# Gero_Board2.net
KiCad netlist of a schematic drawn in Altium Designer
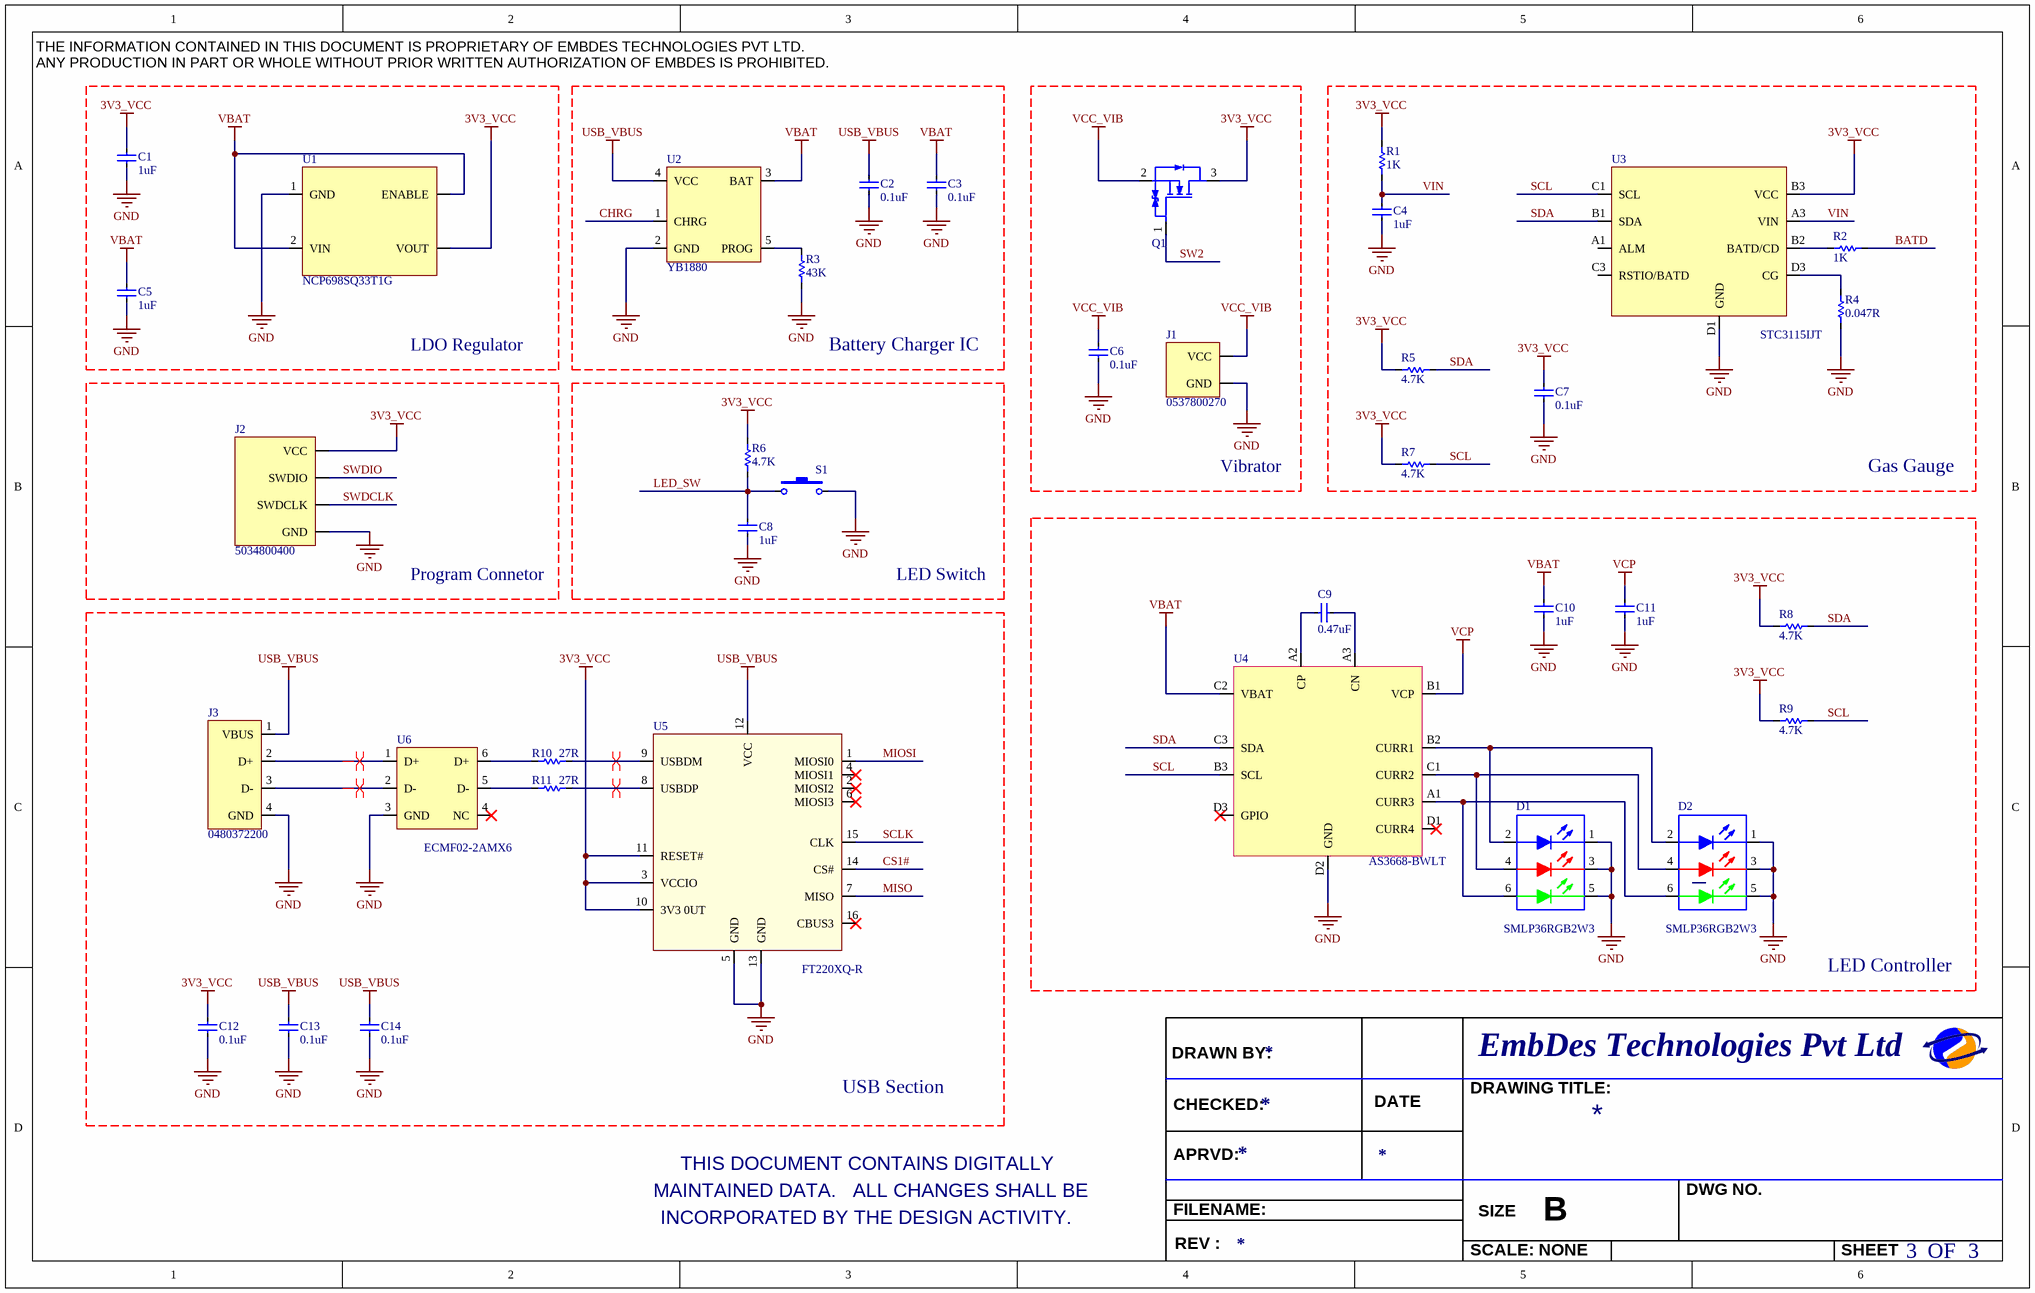
[diagram p0: Gero_Board2.SchDoc]

(export (version "E")
  (design (tool "Eeschema 10.0.6"))
  (components
    (comp (ref "C1")
      (value "1uF")
      (footprint "CAPC1005X04L")
      (description "CAP CER 1UF 16V 10% X5R 0402")
      (fields
        (field (name "MANUFACTURER") "TDK Corporation")
        (field (name "MANUFACTURER PART NUMBER") "C1005X5R1C105K050BC")
      )
      (libsource (lib "Gero_Board.~(283)") (part "CAP CER 1UF 16V 10% X5R 0402"))
    )
    (comp (ref "C2")
      (value "0.1uF")
      (footprint "CAPC1005X04L")
      (description "CAP CER 0.1UF 16V 10% X5R 0201")
      (fields
        (field (name "MANUFACTURER") "TDK Corporation")
        (field (name "MANUFACTURER PART NUMBER") "C0603X5R1C104K030BC")
      )
      (libsource (lib "Gero_Board") (part "CAP CER 0.1UF 16V 10% X5R 0201"))
    )
    (comp (ref "C3")
      (value "0.1uF")
      (footprint "CAPC1005X04L")
      (description "CAP CER 0.1UF 16V 10% X5R 0201")
      (fields
        (field (name "MANUFACTURER") "TDK Corporation")
        (field (name "MANUFACTURER PART NUMBER") "C0603X5R1C104K030BC")
      )
      (libsource (lib "Gero_Board") (part "CAP CER 0.1UF 16V 10% X5R 0201"))
    )
    (comp (ref "C4")
      (value "1uF")
      (footprint "CAPC1005X04L")
      (description "CAP CER 1UF 16V 10% X5R 0402")
      (fields
        (field (name "MANUFACTURER") "TDK Corporation")
        (field (name "MANUFACTURER PART NUMBER") "C1005X5R1C105K050BC")
      )
      (libsource (lib "Gero_Board.~(283)") (part "CAP CER 1UF 16V 10% X5R 0402"))
    )
    (comp (ref "C5")
      (value "1uF")
      (footprint "CAPC1005X04L")
      (description "CAP CER 1UF 16V 10% X5R 0402")
      (fields
        (field (name "MANUFACTURER") "TDK Corporation")
        (field (name "MANUFACTURER PART NUMBER") "C1005X5R1C105K050BC")
      )
      (libsource (lib "Gero_Board.~(283)") (part "CAP CER 1UF 16V 10% X5R 0402"))
    )
    (comp (ref "C6")
      (value "0.1uF")
      (footprint "CAPC1005X04L")
      (description "CAP CER 0.1UF 16V 10% X5R 0201")
      (fields
        (field (name "MANUFACTURER") "TDK Corporation")
        (field (name "MANUFACTURER PART NUMBER") "C0603X5R1C104K030BC")
      )
      (libsource (lib "Gero_Board") (part "CAP CER 0.1UF 16V 10% X5R 0201"))
    )
    (comp (ref "C7")
      (value "0.1uF")
      (footprint "CAPC1005X04L")
      (description "CAP CER 0.1UF 16V 10% X5R 0201")
      (fields
        (field (name "MANUFACTURER") "TDK Corporation")
        (field (name "MANUFACTURER PART NUMBER") "C0603X5R1C104K030BC")
      )
      (libsource (lib "Gero_Board") (part "CAP CER 0.1UF 16V 10% X5R 0201"))
    )
    (comp (ref "C8")
      (value "1uF")
      (footprint "CAPC1005X04L")
      (description "CAP CER 1UF 16V 10% X5R 0402")
      (fields
        (field (name "MANUFACTURER") "TDK Corporation")
        (field (name "MANUFACTURER PART NUMBER") "C1005X5R1C105K050BC")
      )
      (libsource (lib "Gero_Board.~(283)") (part "CAP CER 1UF 16V 10% X5R 0402"))
    )
    (comp (ref "C9")
      (value "0.47uF")
      (footprint "CAPC1005X04L")
      (description "CAP CER 0.47UF 10V 20% JB 0201")
      (fields
        (field (name "MANUFACTURER") "TDK Corporation")
        (field (name "MANUFACTURER PART NUMBER") "C0603JB1A474M030BC")
      )
      (libsource (lib "Gero_Board") (part "CAP CER 0.47UF 10V 20% JB 0201"))
    )
    (comp (ref "C10")
      (value "1uF")
      (footprint "CAPC1005X04L")
      (description "CAP CER 1UF 16V 10% X5R 0402")
      (fields
        (field (name "MANUFACTURER") "TDK Corporation")
        (field (name "MANUFACTURER PART NUMBER") "C1005X5R1C105K050BC")
      )
      (libsource (lib "Gero_Board.~(283)") (part "CAP CER 1UF 16V 10% X5R 0402"))
    )
    (comp (ref "C11")
      (value "1uF")
      (footprint "CAPC1005X04L")
      (description "CAP CER 1UF 16V 10% X5R 0402")
      (fields
        (field (name "MANUFACTURER") "TDK Corporation")
        (field (name "MANUFACTURER PART NUMBER") "C1005X5R1C105K050BC")
      )
      (libsource (lib "Gero_Board.~(283)") (part "CAP CER 1UF 16V 10% X5R 0402"))
    )
    (comp (ref "C12")
      (value "0.1uF")
      (footprint "CAPC1005X04L")
      (description "CAP CER 0.1UF 16V 10% X5R 0201")
      (fields
        (field (name "MANUFACTURER") "TDK Corporation")
        (field (name "MANUFACTURER PART NUMBER") "C0603X5R1C104K030BC")
      )
      (libsource (lib "Gero_Board") (part "CAP CER 0.1UF 16V 10% X5R 0201"))
    )
    (comp (ref "C13")
      (value "0.1uF")
      (footprint "CAPC1005X04L")
      (description "CAP CER 0.1UF 16V 10% X5R 0201")
      (fields
        (field (name "MANUFACTURER") "TDK Corporation")
        (field (name "MANUFACTURER PART NUMBER") "C0603X5R1C104K030BC")
      )
      (libsource (lib "Gero_Board") (part "CAP CER 0.1UF 16V 10% X5R 0201"))
    )
    (comp (ref "C14")
      (value "0.1uF")
      (footprint "CAPC1005X04L")
      (description "CAP CER 0.1UF 16V 10% X5R 0201")
      (fields
        (field (name "MANUFACTURER") "TDK Corporation")
        (field (name "MANUFACTURER PART NUMBER") "C0603X5R1C104K030BC")
      )
      (libsource (lib "Gero_Board") (part "CAP CER 0.1UF 16V 10% X5R 0201"))
    )
    (comp (ref "D1")
      (value "LED PICOLED RGB 5MA 1510")
      (footprint "VLMG1300-GS08")
      (fields
        (field (name "MANUFACTURER") "Rohm Semiconductor")
        (field (name "MANUFACTURER PART NUMBER") "SMLP36RGB2W3")
      )
      (libsource (lib "Gero_Board") (part "LED PICOLED RGB 5MA 1510"))
    )
    (comp (ref "D2")
      (value "LED PICOLED RGB 5MA 1510")
      (footprint "VLMG1300-GS08")
      (fields
        (field (name "MANUFACTURER") "Rohm Semiconductor")
        (field (name "MANUFACTURER PART NUMBER") "SMLP36RGB2W3")
      )
      (libsource (lib "Gero_Board") (part "LED PICOLED RGB 5MA 1510"))
    )
    (comp (ref "J1")
      (value "CONN HEADER 2POS 1.25MM R/A SMD")
      (fields
        (field (name "MANUFACTURER") "Molex Inc")
        (field (name "MANUFACTURER PART NUMBER") "0537800270")
      )
      (libsource (lib "Gero_Board") (part "CONN HEADER 2POS 1.25MM R/A SMD"))
    )
    (comp (ref "J2")
      (value "CONN .5MM FPC 4POS RA SMD B-FLIP")
      (fields
        (field (name "MANUFACTURER") "Molex Inc")
        (field (name "MANUFACTURER PART NUMBER") "5034800400")
      )
      (libsource (lib "Gero_Board") (part "CONN .5MM FPC 4POS RA SMD B-FLIP"))
    )
    (comp (ref "J3")
      (value "CONN PLUG USB A 4POS SMD R/A")
      (fields
        (field (name "MANUFACTURER") "Molex Inc")
        (field (name "MANUFACTURER PART NUMBER") "0480372200")
      )
      (libsource (lib "Gero_Board.~(283)") (part "CONN PLUG USB A 4POS SMD R/A"))
    )
    (comp (ref "Q1")
      (value "MOSFET N-CH 20V 200MA 3-DFN")
      (fields (field (name "MANUFACTURER") "Diodes Inc") (field (name "MFG PART NO") "DMN2005LP4K-7"))
      (libsource (lib "Gero_Board.~(283)") (part "MOSFET N-CH 20V 200MA 3-DFN"))
    )
    (comp (ref "R1")
      (value "1K")
      (footprint "R0402")
      (description "RES 1K OHM 1/20W 1% 0201 SMD")
      (libsource (lib "Gero_Board") (part "RES 1K OHM 1/20W 1% 0201 SMD"))
    )
    (comp (ref "R2")
      (value "1K")
      (footprint "R0402")
      (description "RES 1K OHM 1/20W 1% 0201 SMD")
      (libsource (lib "Gero_Board") (part "RES 1K OHM 1/20W 1% 0201 SMD"))
    )
    (comp (ref "R3")
      (value "43K")
      (footprint "R0402")
      (description "RES 43K OHM 1/20W 1% 0201 SMD")
      (fields
        (field (name "MANUFACTURER PART NUMBER") "ERJ-1GEF4302C")
        (field (name "MANUFACTURER") "Panasonic Electronic Components")
      )
      (libsource (lib "Gero_Board") (part "RES 43K OHM 1/20W 1% 0201 SMD"))
    )
    (comp (ref "R4")
      (value "0.047R")
      (footprint "R0402")
      (description "RES 0.047 OHM 1/4W 1% 0402 SMD")
      (libsource (lib "Gero_Board") (part "RES 0.047 OHM 1/4W 1% 0402 SMD"))
    )
    (comp (ref "R5")
      (value "4.7K")
      (footprint "R0402")
      (description "RES 4.7K OHM 1/20W 1% 0201 SMD")
      (fields (field (name "MANUFACTURER") "Panasonic Electronic Components"))
      (libsource (lib "Gero_Board") (part "RES 4.7K OHM 1/20W 1% 0201 SMD"))
    )
    (comp (ref "R6")
      (value "4.7K")
      (footprint "R0402")
      (description "RES 4.7K OHM 1/20W 1% 0201 SMD")
      (fields (field (name "MANUFACTURER") "Panasonic Electronic Components"))
      (libsource (lib "Gero_Board") (part "RES 4.7K OHM 1/20W 1% 0201 SMD"))
    )
    (comp (ref "R7")
      (value "4.7K")
      (footprint "R0402")
      (description "RES 4.7K OHM 1/20W 1% 0201 SMD")
      (fields (field (name "MANUFACTURER") "Panasonic Electronic Components"))
      (libsource (lib "Gero_Board") (part "RES 4.7K OHM 1/20W 1% 0201 SMD"))
    )
    (comp (ref "R8")
      (value "4.7K")
      (footprint "R0402")
      (description "RES 4.7K OHM 1/20W 1% 0201 SMD")
      (fields (field (name "MANUFACTURER") "Panasonic Electronic Components"))
      (libsource (lib "Gero_Board") (part "RES 4.7K OHM 1/20W 1% 0201 SMD"))
    )
    (comp (ref "R9")
      (value "4.7K")
      (footprint "R0402")
      (description "RES 4.7K OHM 1/20W 1% 0201 SMD")
      (fields (field (name "MANUFACTURER") "Panasonic Electronic Components"))
      (libsource (lib "Gero_Board") (part "RES 4.7K OHM 1/20W 1% 0201 SMD"))
    )
    (comp (ref "R10")
      (value "27R")
      (footprint "R0402")
      (description "RES 27 OHM 1/20W 1% 0201 SMD")
      (fields
        (field (name "MANUFACTURER PART NUMBER") "ERJ-1GEF27R0C")
        (field (name "MANUFACTURER") "Panasonic Electronic Components")
      )
      (libsource (lib "Gero_Board") (part "RES 27 OHM 1/20W 1% 0201 SMD"))
    )
    (comp (ref "R11")
      (value "27R")
      (footprint "R0402")
      (description "RES 27 OHM 1/20W 1% 0201 SMD")
      (fields
        (field (name "MANUFACTURER PART NUMBER") "ERJ-1GEF27R0C")
        (field (name "MANUFACTURER") "Panasonic Electronic Components")
      )
      (libsource (lib "Gero_Board") (part "RES 27 OHM 1/20W 1% 0201 SMD"))
    )
    (comp (ref "S1") (value "SW-PB") (description "Switch") (libsource (lib "Gero_Board") (part "SW-PB")))
    (comp (ref "U1")
      (value "IC REG LDO 3.3V 0.28A SC82AB")
      (fields
        (field (name "MANUFACTURER") "ON Semiconductor")
        (field (name "MANUFACTURER PART NUMBER") "NCP698SQ33T1G")
      )
      (libsource (lib "Gero_Board") (part "IC REG LDO 3.3V 0.28A SC82AB"))
    )
    (comp (ref "U2")
      (value "Standalone Linear Lithium Battery Charger")
      (footprint "YB1880ST25P")
      (fields
        (field (name "MANUFACTURER") "YOBON TECHNOLOGIES")
        (field (name "MANUFACTURER PART NUMBER") "YB1880")
      )
      (libsource (lib "Gero_Board.~(283)") (part "Standalone Linear Lithium Battery Charger"))
    )
    (comp (ref "U3")
      (value "IC GAS GAUGE LI-ION/POL 10CSP")
      (footprint "STC3115")
      (fields
        (field (name "MANUFACTURER") "STMicroelectronics")
        (field (name "MANUFACTURER PART NUMBER") "STC3115IJT")
      )
      (libsource (lib "Gero_Board.~(283)") (part "IC GAS GAUGE LI-ION/POL 10CSP"))
    )
    (comp (ref "U4")
      (value "4 Channel Breathlight Controller")
      (footprint "AS3668  CSP 1.3x1.7mm")
      (fields (field (name "MANUFACTURER") "AMS") (field (name "MANUFACTURER PART NUMBER") "AS3668-BWLT"))
      (libsource (lib "Gero_Board.~(283)") (part "4 Channel Breathlight Controller"))
    )
    (comp (ref "U5")
      (value "IC USB 4 BIT SPI/FT1248 16QFN")
      (footprint "FT220 XQ-R")
      (fields
        (field (name "MANUFACTURER") "FTDI, Future Technology Devices International Ltd")
        (field (name "MANUFACTURER PART NUMBER") "FT220XQ-R")
      )
      (libsource (lib "Gero_Board.~(283)") (part "IC USB 4 BIT SPI/FT1248 16QFN"))
    )
    (comp (ref "U6")
      (value "IC ESD FILTER COMM MODE 6-UQFN")
      (fields
        (field (name "MANUFACTURER") "STMicroelectronics")
        (field (name "MANUFACTURER PART NUMBER") "ECMF02-2AMX6")
      )
      (libsource (lib "Gero_Board.~(283)") (part "IC ESD FILTER COMM MODE 6-UQFN"))
    )
  )
  (nets
    (net (code "1") (name "/BATD") (class "Default")
      (node (ref "R2") (pin "1") (pinfunction "1_1") (pintype "passive"))
    )
    (net (code "2") (name "/CHRG") (class "Default")
      (node (ref "U2") (pin "1") (pinfunction "CHRG_1") (pintype "passive"))
    )
    (net (code "3") (name "/CS1#") (class "Default")
      (node (ref "U5") (pin "14") (pinfunction "CS#_14") (pintype "passive"))
    )
    (net (code "4") (name "/LED_SW") (class "Default")
      (node (ref "C8") (pin "2") (pinfunction "2_2") (pintype "passive"))
      (node (ref "R6") (pin "1") (pinfunction "1_1") (pintype "passive"))
      (node (ref "S1") (pin "1") (pinfunction "1_1") (pintype "passive"))
    )
    (net (code "5") (name "/MIOSI") (class "Default")
      (node (ref "U5") (pin "1") (pinfunction "MIOSI0_1") (pintype "passive"))
    )
    (net (code "6") (name "/MISO") (class "Default")
      (node (ref "U5") (pin "7") (pinfunction "MISO_7") (pintype "passive"))
    )
    (net (code "7") (name "/SCL") (class "Default")
      (node (ref "R7") (pin "2") (pinfunction "2_2") (pintype "passive"))
      (node (ref "R9") (pin "2") (pinfunction "2_2") (pintype "passive"))
      (node (ref "U3") (pin "C1") (pinfunction "SCL_C1") (pintype "passive"))
      (node (ref "U4") (pin "B3") (pinfunction "SCL_B3") (pintype "passive"))
    )
    (net (code "8") (name "/SCLK") (class "Default")
      (node (ref "U5") (pin "15") (pinfunction "CLK_15") (pintype "passive"))
    )
    (net (code "9") (name "/SDA") (class "Default")
      (node (ref "R5") (pin "2") (pinfunction "2_2") (pintype "passive"))
      (node (ref "R8") (pin "2") (pinfunction "2_2") (pintype "passive"))
      (node (ref "U3") (pin "B1") (pinfunction "SDA_B1") (pintype "passive"))
      (node (ref "U4") (pin "C3") (pinfunction "SDA_C3") (pintype "passive"))
    )
    (net (code "10") (name "/SW2") (class "Default")
      (node (ref "Q1") (pin "1") (pinfunction "G_1") (pintype "passive"))
    )
    (net (code "11") (name "/SWDCLK") (class "Default")
      (node (ref "J2") (pin "3") (pinfunction "SWDCLK_3") (pintype "passive"))
    )
    (net (code "12") (name "/SWDIO") (class "Default")
      (node (ref "J2") (pin "2") (pinfunction "SWDIO_2") (pintype "passive"))
    )
    (net (code "13") (name "/VIN") (class "Default")
      (node (ref "C4") (pin "1") (pinfunction "1_1") (pintype "passive"))
      (node (ref "R1") (pin "1") (pinfunction "1_1") (pintype "passive"))
      (node (ref "U3") (pin "A3") (pinfunction "VIN_A3") (pintype "passive"))
    )
    (net (code "14") (name "3V3_VCC") (class "Default")
      (node (ref "C1") (pin "2") (pinfunction "2_2") (pintype "passive"))
      (node (ref "C12") (pin "2") (pinfunction "2_2") (pintype "passive"))
      (node (ref "C7") (pin "2") (pinfunction "2_2") (pintype "passive"))
      (node (ref "J2") (pin "1") (pinfunction "VCC_1") (pintype "passive"))
      (node (ref "Q1") (pin "3") (pinfunction "D_3") (pintype "passive"))
      (node (ref "R1") (pin "2") (pinfunction "2_2") (pintype "passive"))
      (node (ref "R5") (pin "1") (pinfunction "1_1") (pintype "passive"))
      (node (ref "R6") (pin "2") (pinfunction "2_2") (pintype "passive"))
      (node (ref "R7") (pin "1") (pinfunction "1_1") (pintype "passive"))
      (node (ref "R8") (pin "1") (pinfunction "1_1") (pintype "passive"))
      (node (ref "R9") (pin "1") (pinfunction "1_1") (pintype "passive"))
      (node (ref "U1") (pin "4") (pinfunction "VOUT_4") (pintype "passive"))
      (node (ref "U3") (pin "B3") (pinfunction "VCC_B3") (pintype "passive"))
      (node (ref "U5") (pin "10") (pinfunction "3V3_0UT_10") (pintype "passive"))
      (node (ref "U5") (pin "11") (pinfunction "RESET#_11") (pintype "passive"))
      (node (ref "U5") (pin "3") (pinfunction "VCCIO_3") (pintype "passive"))
    )
    (net (code "15") (name "GND") (class "Default")
      (node (ref "C1") (pin "1") (pinfunction "1_1") (pintype "passive"))
      (node (ref "C10") (pin "1") (pinfunction "1_1") (pintype "passive"))
      (node (ref "C11") (pin "1") (pinfunction "1_1") (pintype "passive"))
      (node (ref "C12") (pin "1") (pinfunction "1_1") (pintype "passive"))
      (node (ref "C13") (pin "1") (pinfunction "1_1") (pintype "passive"))
      (node (ref "C14") (pin "1") (pinfunction "1_1") (pintype "passive"))
      (node (ref "C2") (pin "1") (pinfunction "1_1") (pintype "passive"))
      (node (ref "C3") (pin "1") (pinfunction "1_1") (pintype "passive"))
      (node (ref "C4") (pin "2") (pinfunction "2_2") (pintype "passive"))
      (node (ref "C5") (pin "1") (pinfunction "1_1") (pintype "passive"))
      (node (ref "C6") (pin "1") (pinfunction "1_1") (pintype "passive"))
      (node (ref "C7") (pin "1") (pinfunction "1_1") (pintype "passive"))
      (node (ref "C8") (pin "1") (pinfunction "1_1") (pintype "passive"))
      (node (ref "D1") (pin "1") (pinfunction "K_1") (pintype "passive"))
      (node (ref "D1") (pin "3") (pinfunction "K_3") (pintype "passive"))
      (node (ref "D1") (pin "5") (pinfunction "K_5") (pintype "passive"))
      (node (ref "D2") (pin "1") (pinfunction "K_1") (pintype "passive"))
      (node (ref "D2") (pin "3") (pinfunction "K_3") (pintype "passive"))
      (node (ref "D2") (pin "5") (pinfunction "K_5") (pintype "passive"))
      (node (ref "J1") (pin "2") (pinfunction "GND_2") (pintype "passive"))
      (node (ref "J2") (pin "4") (pinfunction "GND_4") (pintype "passive"))
      (node (ref "J3") (pin "4") (pinfunction "GND_4") (pintype "passive"))
      (node (ref "R3") (pin "1") (pinfunction "1_1") (pintype "passive"))
      (node (ref "R4") (pin "1") (pinfunction "1_1") (pintype "passive"))
      (node (ref "S1") (pin "2") (pinfunction "2_2") (pintype "passive"))
      (node (ref "U1") (pin "1") (pinfunction "GND_1") (pintype "passive"))
      (node (ref "U2") (pin "2") (pinfunction "GND_2") (pintype "passive"))
      (node (ref "U3") (pin "D1") (pinfunction "GND_D1") (pintype "passive"))
      (node (ref "U4") (pin "D2") (pinfunction "GND_D2") (pintype "passive"))
      (node (ref "U5") (pin "13") (pinfunction "GND_13") (pintype "passive"))
      (node (ref "U5") (pin "5") (pinfunction "GND_5") (pintype "passive"))
      (node (ref "U6") (pin "3") (pinfunction "GND_3") (pintype "passive"))
    )
    (net (code "16") (name "Net-(J3-D+)") (class "Default")
      (node (ref "J3") (pin "2") (pinfunction "D+_2") (pintype "passive"))
      (node (ref "U6") (pin "1") (pinfunction "D+_1") (pintype "passive"))
    )
    (net (code "17") (name "Net-(J3-D-)") (class "Default")
      (node (ref "J3") (pin "3") (pinfunction "D-_3") (pintype "passive"))
      (node (ref "U6") (pin "2") (pinfunction "D-_2") (pintype "passive"))
    )
    (net (code "18") (name "Net-(R10-Pad1)") (class "Default")
      (node (ref "R10") (pin "1") (pinfunction "1_1") (pintype "passive"))
      (node (ref "U6") (pin "6") (pinfunction "D+_6") (pintype "passive"))
    )
    (net (code "19") (name "Net-(R11-Pad1)") (class "Default")
      (node (ref "R11") (pin "1") (pinfunction "1_1") (pintype "passive"))
      (node (ref "U6") (pin "5") (pinfunction "D-_5") (pintype "passive"))
    )
    (net (code "20") (name "Net-(U2-PROG)") (class "Default")
      (node (ref "R3") (pin "2") (pinfunction "2_2") (pintype "passive"))
      (node (ref "U2") (pin "5") (pinfunction "PROG_5") (pintype "passive"))
    )
    (net (code "21") (name "Net-(U3-BATD{slash}CD)") (class "Default")
      (node (ref "R2") (pin "2") (pinfunction "2_2") (pintype "passive"))
      (node (ref "U3") (pin "B2") (pinfunction "BATD/CD_B2") (pintype "passive"))
    )
    (net (code "22") (name "Net-(U3-CG)") (class "Default")
      (node (ref "R4") (pin "2") (pinfunction "2_2") (pintype "passive"))
      (node (ref "U3") (pin "D3") (pinfunction "CG_D3") (pintype "passive"))
    )
    (net (code "23") (name "Net-(U4-CN)") (class "Default")
      (node (ref "C9") (pin "2") (pinfunction "2_2") (pintype "passive"))
      (node (ref "U4") (pin "A3") (pinfunction "CN_A3") (pintype "passive"))
    )
    (net (code "24") (name "Net-(U4-CP)") (class "Default")
      (node (ref "C9") (pin "1") (pinfunction "1_1") (pintype "passive"))
      (node (ref "U4") (pin "A2") (pinfunction "CP_A2") (pintype "passive"))
    )
    (net (code "25") (name "Net-(U4-CURR1)") (class "Default")
      (node (ref "D1") (pin "2") (pinfunction "A_2") (pintype "passive"))
      (node (ref "D2") (pin "2") (pinfunction "A_2") (pintype "passive"))
      (node (ref "U4") (pin "B2") (pinfunction "CURR1_B2") (pintype "passive"))
    )
    (net (code "26") (name "Net-(U4-CURR2)") (class "Default")
      (node (ref "D1") (pin "4") (pinfunction "A_4") (pintype "passive"))
      (node (ref "D2") (pin "4") (pinfunction "A_4") (pintype "passive"))
      (node (ref "U4") (pin "C1") (pinfunction "CURR2_C1") (pintype "passive"))
    )
    (net (code "27") (name "Net-(U4-CURR3)") (class "Default")
      (node (ref "D1") (pin "6") (pinfunction "A_6") (pintype "passive"))
      (node (ref "D2") (pin "6") (pinfunction "A_6") (pintype "passive"))
      (node (ref "U4") (pin "A1") (pinfunction "CURR3_A1") (pintype "passive"))
    )
    (net (code "28") (name "Net-(U5-USBDM)") (class "Default")
      (node (ref "R10") (pin "2") (pinfunction "2_2") (pintype "passive"))
      (node (ref "U5") (pin "9") (pinfunction "USBDM_9") (pintype "passive"))
    )
    (net (code "29") (name "Net-(U5-USBDP)") (class "Default")
      (node (ref "R11") (pin "2") (pinfunction "2_2") (pintype "passive"))
      (node (ref "U5") (pin "8") (pinfunction "USBDP_8") (pintype "passive"))
    )
    (net (code "30") (name "USB_VBUS") (class "Default")
      (node (ref "C13") (pin "2") (pinfunction "2_2") (pintype "passive"))
      (node (ref "C14") (pin "2") (pinfunction "2_2") (pintype "passive"))
      (node (ref "C2") (pin "2") (pinfunction "2_2") (pintype "passive"))
      (node (ref "J3") (pin "1") (pinfunction "VBUS_1") (pintype "passive"))
      (node (ref "U2") (pin "4") (pinfunction "VCC_4") (pintype "passive"))
      (node (ref "U5") (pin "12") (pinfunction "VCC_12") (pintype "passive"))
    )
    (net (code "31") (name "VBAT") (class "Default")
      (node (ref "C10") (pin "2") (pinfunction "2_2") (pintype "passive"))
      (node (ref "C3") (pin "2") (pinfunction "2_2") (pintype "passive"))
      (node (ref "C5") (pin "2") (pinfunction "2_2") (pintype "passive"))
      (node (ref "U1") (pin "2") (pinfunction "VIN_2") (pintype "passive"))
      (node (ref "U1") (pin "3") (pinfunction "ENABLE_3") (pintype "passive"))
      (node (ref "U2") (pin "3") (pinfunction "BAT_3") (pintype "passive"))
      (node (ref "U4") (pin "C2") (pinfunction "VBAT_C2") (pintype "passive"))
    )
    (net (code "32") (name "VCC_VIB") (class "Default")
      (node (ref "C6") (pin "2") (pinfunction "2_2") (pintype "passive"))
      (node (ref "J1") (pin "1") (pinfunction "VCC_1") (pintype "passive"))
      (node (ref "Q1") (pin "2") (pinfunction "S_2") (pintype "passive"))
    )
    (net (code "33") (name "VCP") (class "Default")
      (node (ref "C11") (pin "2") (pinfunction "2_2") (pintype "passive"))
      (node (ref "U4") (pin "B1") (pinfunction "VCP_B1") (pintype "passive"))
    )
    (net (code "34") (name "unconnected-(U3-ALM-PadA1)") (class "Default")
      (node (ref "U3") (pin "A1") (pinfunction "ALM_A1") (pintype "passive"))
    )
    (net (code "35") (name "unconnected-(U3-RSTIO{slash}BATD-PadC3)") (class "Default")
      (node (ref "U3") (pin "C3") (pinfunction "RSTIO/BATD_C3") (pintype "passive"))
    )
    (net (code "36") (name "unconnected-(U4-CURR4-PadD1)") (class "Default")
      (node (ref "U4") (pin "D1") (pinfunction "CURR4_D1") (pintype "passive+no_connect"))
    )
    (net (code "37") (name "unconnected-(U4-GPIO-PadD3)") (class "Default")
      (node (ref "U4") (pin "D3") (pinfunction "GPIO_D3") (pintype "passive+no_connect"))
    )
    (net (code "38") (name "unconnected-(U5-CBUS3-Pad16)") (class "Default")
      (node (ref "U5") (pin "16") (pinfunction "CBUS3_16") (pintype "passive+no_connect"))
    )
    (net (code "39") (name "unconnected-(U5-MIOSI1-Pad4)") (class "Default")
      (node (ref "U5") (pin "4") (pinfunction "MIOSI1_4") (pintype "passive+no_connect"))
    )
    (net (code "40") (name "unconnected-(U5-MIOSI2-Pad2)") (class "Default")
      (node (ref "U5") (pin "2") (pinfunction "MIOSI2_2") (pintype "passive+no_connect"))
    )
    (net (code "41") (name "unconnected-(U5-MIOSI3-Pad6)") (class "Default")
      (node (ref "U5") (pin "6") (pinfunction "MIOSI3_6") (pintype "passive+no_connect"))
    )
    (net (code "42") (name "unconnected-(U6-NC-Pad4)") (class "Default")
      (node (ref "U6") (pin "4") (pinfunction "NC_4") (pintype "passive+no_connect"))
    )
  )
)
